# Button_PCB_for_BikeLapse_Camera_Trigger_.net
KiCad netlist of a schematic drawn in EAGLE
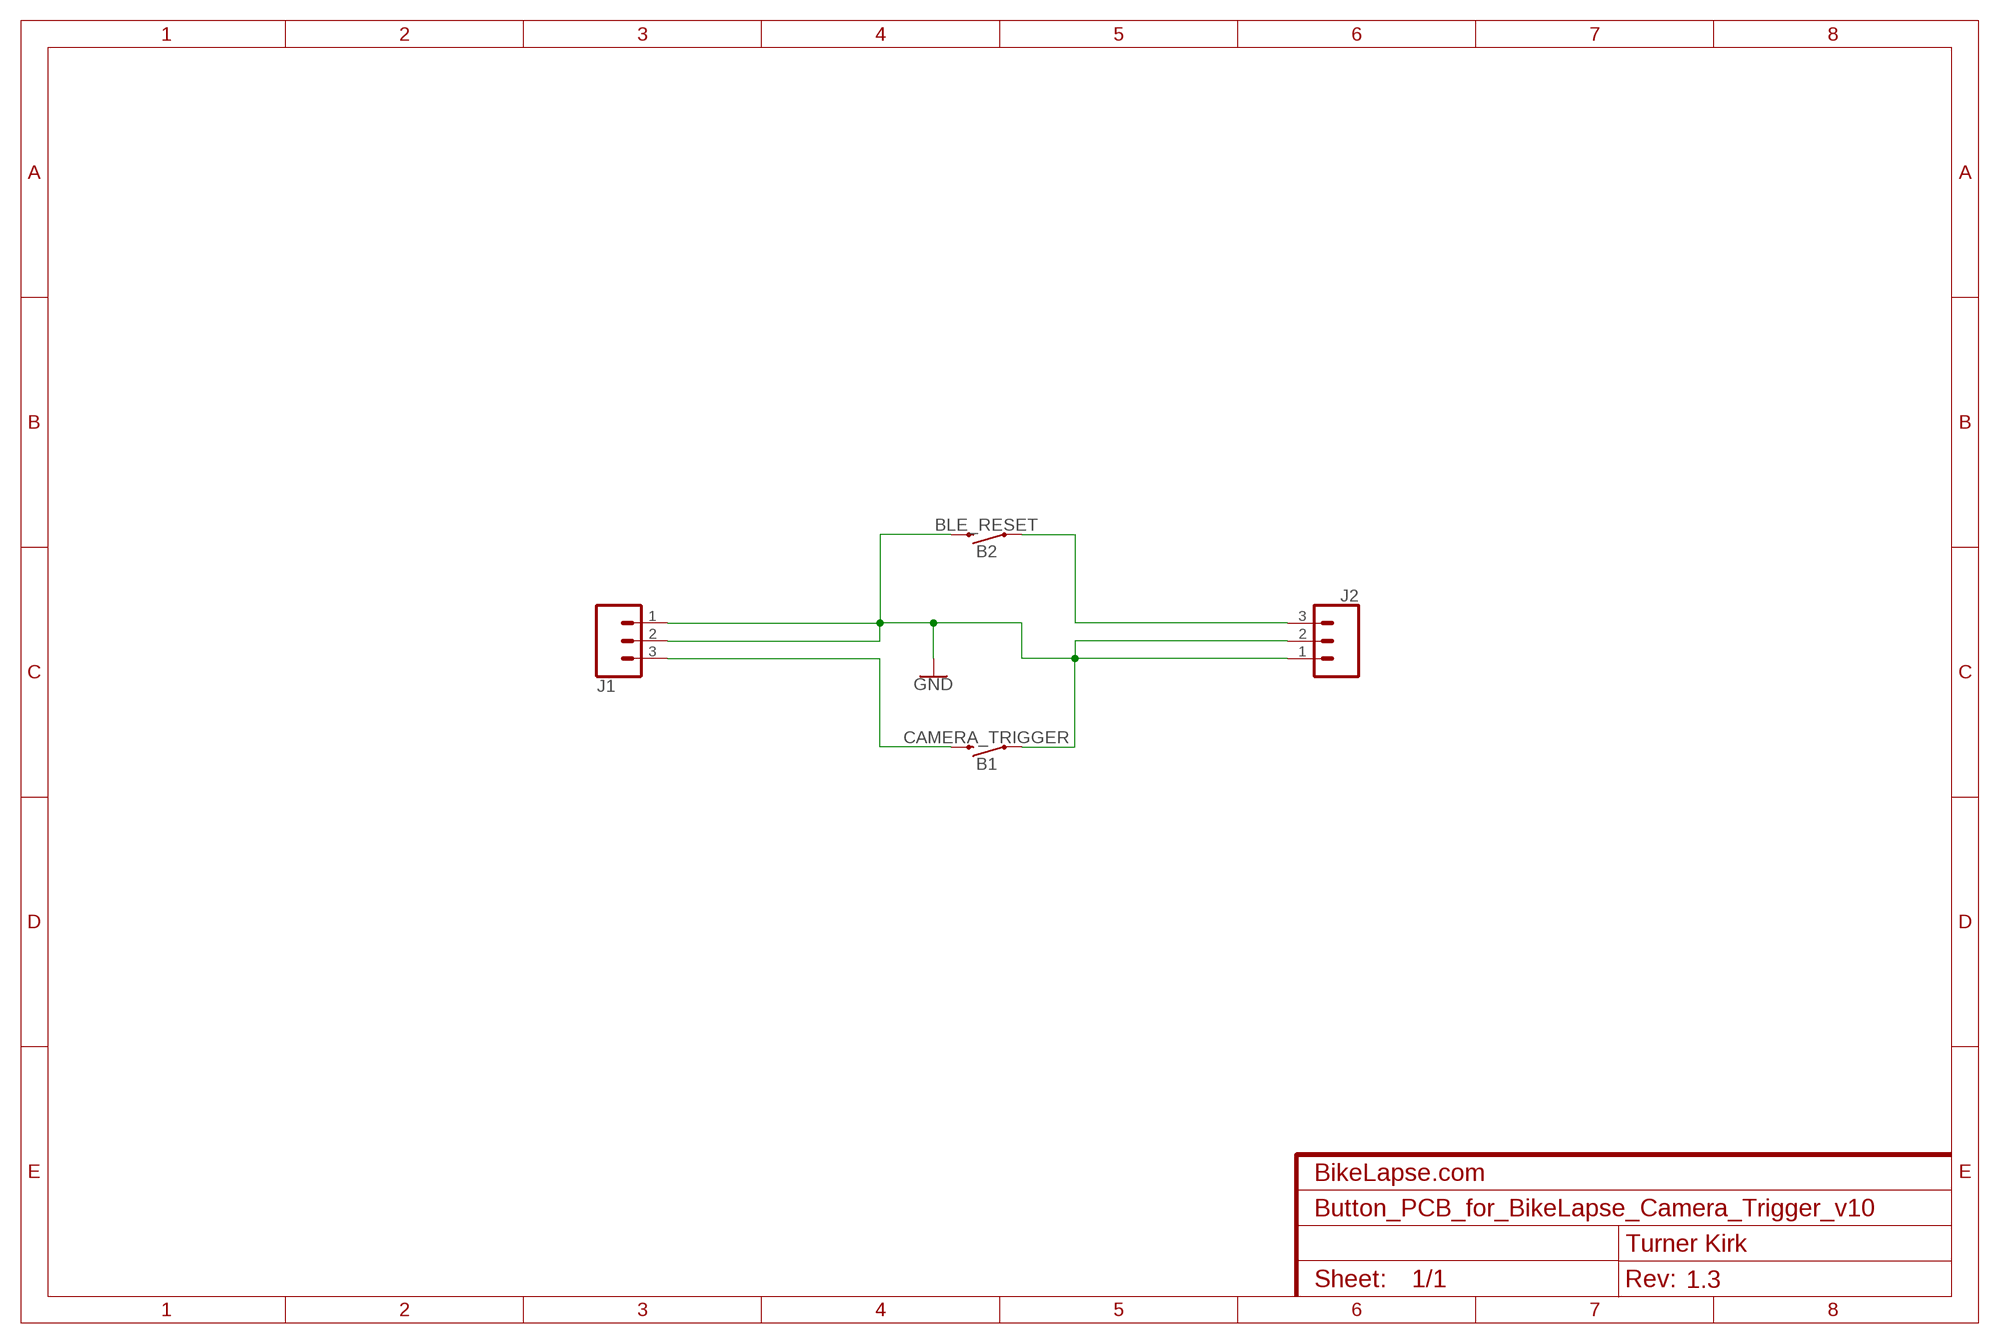
[diagram p0: schematic, sheet 1]

(export (version "E")
  (design (tool "Eeschema 10.0.6"))
  (components
    (comp (ref "B1")
      (value "CAMERA_TRIGGER")
      (footprint "eagle-import:TACTILE_SWITCH_PTH_12MM")
      (libsource (lib "eagle-import") (part "MOMENTARY-SWITCH-SPST-PTH-12MM"))
    )
    (comp (ref "B2")
      (value "BLE_RESET")
      (footprint "eagle-import:TACTILE_SWITCH_PTH_6.0MM")
      (libsource (lib "eagle-import") (part "MOMENTARY-SWITCH-SPST-PTH-6.0MM"))
    )
    (comp (ref "J1")
      (value "455-1750-1-ND")
      (footprint "eagle-import:1X03-MALE_HEADERS_BOTTOM")
      (libsource (lib "eagle-import") (part "CONN_03MALE_HEADERS_BOTTOM"))
    )
    (comp (ref "J2")
      (value "455-1750-1-ND")
      (footprint "eagle-import:1X03-MALE_HEADERS_BOTTOM")
      (libsource (lib "eagle-import") (part "CONN_03MALE_HEADERS_BOTTOM"))
    )
  )
  (nets
    (net (code "1") (name "GND") (class "Default")
      (node (ref "B1") (pin "1") (pinfunction "1_1") (pintype "passive"))
      (node (ref "B2") (pin "3") (pinfunction "2_3") (pintype "passive"))
      (node (ref "J1") (pin "1") (pinfunction "1_1") (pintype "passive"))
      (node (ref "J1") (pin "2") (pinfunction "2_2") (pintype "passive"))
      (node (ref "J2") (pin "1") (pinfunction "1_1") (pintype "passive"))
      (node (ref "J2") (pin "2") (pinfunction "2_2") (pintype "passive"))
    )
    (net (code "2") (name "Net-(B1-2)") (class "Default")
      (node (ref "B1") (pin "3") (pinfunction "2_3") (pintype "passive"))
      (node (ref "J1") (pin "3") (pinfunction "3_3") (pintype "passive"))
    )
    (net (code "3") (name "Net-(B2-Pad1)") (class "Default")
      (node (ref "B2") (pin "1") (pinfunction "1_1") (pintype "passive"))
      (node (ref "J2") (pin "3") (pinfunction "3_3") (pintype "passive"))
    )
  )
)
